# Straingauge.net
KiCad netlist of a schematic drawn in Altium Designer
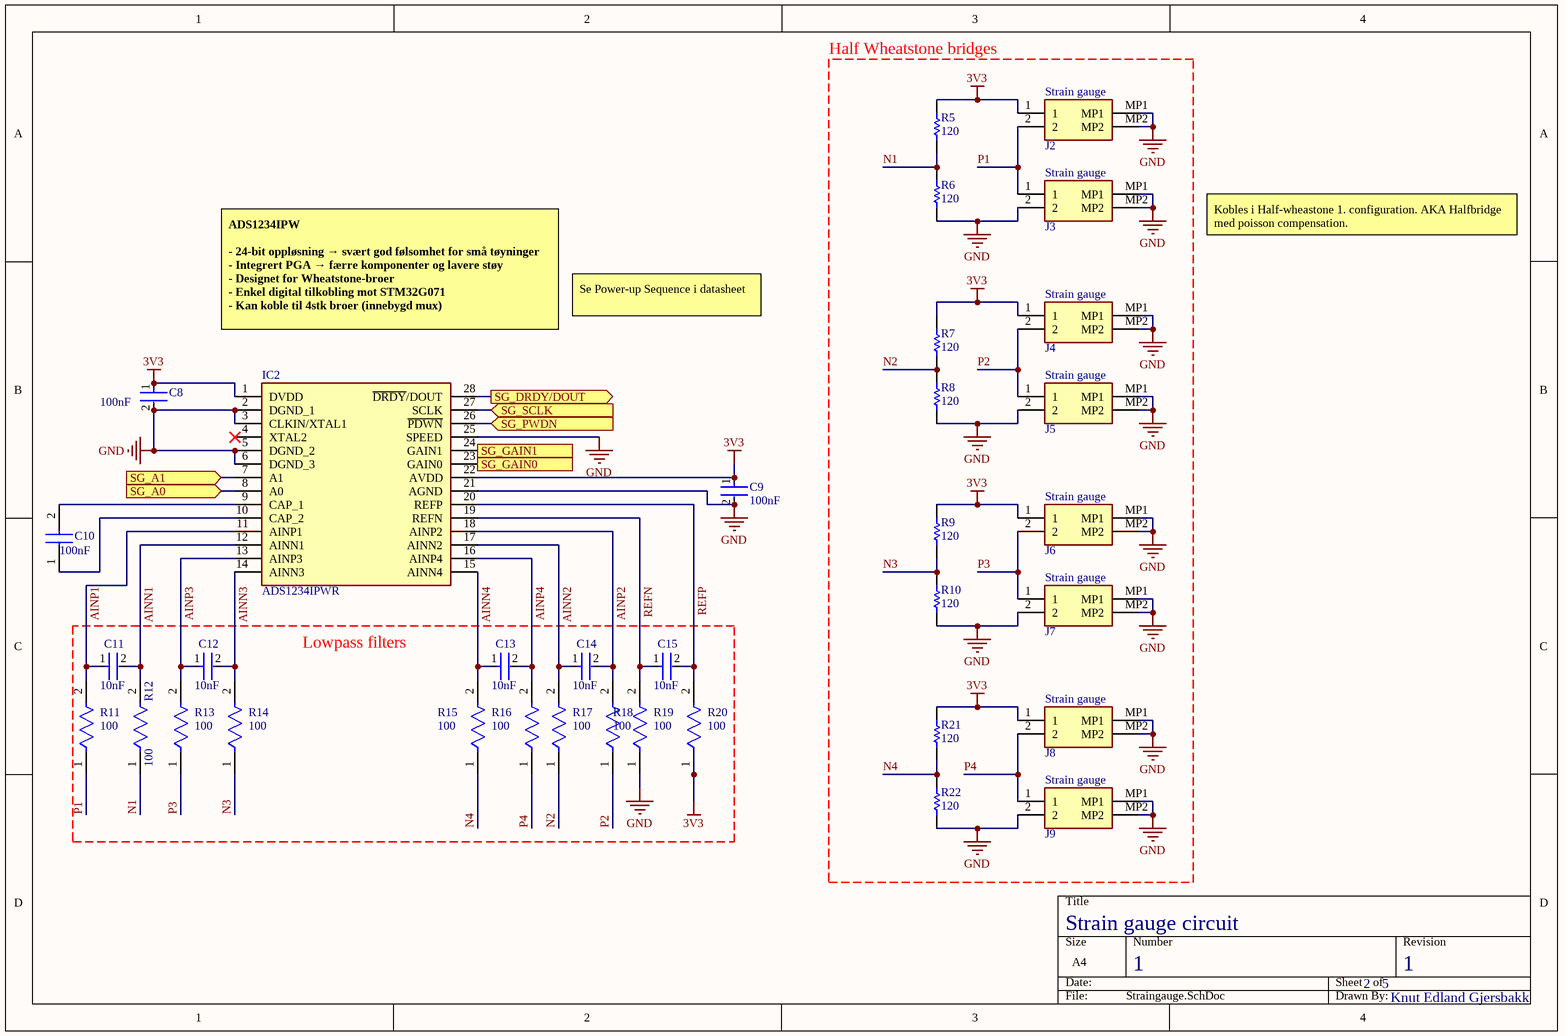
[diagram p0: Straingauge.SchDoc]

(export (version "E")
  (design (tool "Eeschema 10.0.6"))
  (components
    (comp (ref "C8")
      (value "100nF")
      (footprint "FP-CL10-IPC_C")
      (description "Cap Ceramic 100nF 16V X7R ±10% Pad SMD 0603 +125°C T/R\r\nCL10B104KO8WPNC")
      (fields (field (name "TOLERANCE") "10%"))
      (libsource (lib "Altium Content Vault") (part "b4654b650e69147ec39a6b967a45e02"))
    )
    (comp (ref "C9")
      (value "100nF")
      (footprint "FP-CL10-IPC_C")
      (description "Cap Ceramic 100nF 16V X7R ±10% Pad SMD 0603 +125°C T/R\r\nCL10B104KO8WPNC")
      (fields (field (name "TOLERANCE") "10%"))
      (libsource (lib "Altium Content Vault") (part "b4654b650e69147ec39a6b967a45e02"))
    )
    (comp (ref "C10")
      (value "100nF")
      (footprint "SamacSys:CAPC3216X180N")
      (description "Capacitor")
      (fields
        (field (name "MANUFACTURER_PART_NUMBER") "GRM31C5C1E104JA01L")
        (field (name "MOUSER PART NUMBER") "81-GRM31C5C1E104JA01")
      )
      (libsource (lib "*") (part "GRM31C5C1E104JA01L"))
    )
    (comp (ref "C11")
      (value "GRM2195C1H103JA01D")
      (footprint "FP-GRM219-0_1-IPC_B")
      (description "Chip Multilayer Ceramic Capacitors for General Purpose, 0805, 10000pF, C0G, 30ppm/°C, 5%, 50V")
      (fields
        (field (name "VOLTAGE") "50V")
        (field (name "TOLERANCE") "5%")
        (field (name "CAPACITANCE") "10nF")
      )
      (libsource (lib "Altium Content Vault") (part "02cd4be3c70576c341d710602a673aa"))
    )
    (comp (ref "C12")
      (value "GRM2195C1H103JA01D")
      (footprint "FP-GRM219-0_1-IPC_B")
      (description "Chip Multilayer Ceramic Capacitors for General Purpose, 0805, 10000pF, C0G, 30ppm/°C, 5%, 50V")
      (fields
        (field (name "VOLTAGE") "50V")
        (field (name "TOLERANCE") "5%")
        (field (name "CAPACITANCE") "10nF")
      )
      (libsource (lib "Altium Content Vault") (part "02cd4be3c70576c341d710602a673aa"))
    )
    (comp (ref "C13")
      (value "GRM2195C1H103JA01D")
      (footprint "FP-GRM219-0_1-IPC_B")
      (description "Chip Multilayer Ceramic Capacitors for General Purpose, 0805, 10000pF, C0G, 30ppm/°C, 5%, 50V")
      (fields
        (field (name "VOLTAGE") "50V")
        (field (name "TOLERANCE") "5%")
        (field (name "CAPACITANCE") "10nF")
      )
      (libsource (lib "Altium Content Vault") (part "02cd4be3c70576c341d710602a673aa"))
    )
    (comp (ref "C14")
      (value "GRM2195C1H103JA01D")
      (footprint "FP-GRM219-0_1-IPC_B")
      (description "Chip Multilayer Ceramic Capacitors for General Purpose, 0805, 10000pF, C0G, 30ppm/°C, 5%, 50V")
      (fields
        (field (name "VOLTAGE") "50V")
        (field (name "TOLERANCE") "5%")
        (field (name "CAPACITANCE") "10nF")
      )
      (libsource (lib "Altium Content Vault") (part "02cd4be3c70576c341d710602a673aa"))
    )
    (comp (ref "C15")
      (value "GRM2195C1H103JA01D")
      (footprint "FP-GRM219-0_1-IPC_B")
      (description "Chip Multilayer Ceramic Capacitors for General Purpose, 0805, 10000pF, C0G, 30ppm/°C, 5%, 50V")
      (fields
        (field (name "VOLTAGE") "50V")
        (field (name "TOLERANCE") "5%")
        (field (name "CAPACITANCE") "10nF")
      )
      (libsource (lib "Altium Content Vault") (part "02cd4be3c70576c341d710602a673aa"))
    )
    (comp (ref "IC2")
      (value "ADS1234IPWR")
      (footprint "SamacSys:SOP65P640X120-28N")
      (description "Integrated Circuit")
      (fields (field (name "MOUSER PART NUMBER") "595-ADS1234IPWR"))
      (libsource (lib "*") (part "ADS1234IPWR"))
    )
    (comp (ref "J2")
      (value "S2B-PH-SM4-TB_LF__SN_")
      (footprint "SamacSys:S2BPHSM4TBLFSN")
      (description "Connector")
      (fields (field (name "MANUFACTURER_PART_NUMBER") "S2B-PH-SM4-TB(LF)(SN)"))
      (libsource (lib "*") (part "S2B-PH-SM4-TB_LF__SN_"))
    )
    (comp (ref "J3")
      (value "S2B-PH-SM4-TB_LF__SN_")
      (footprint "SamacSys:S2BPHSM4TBLFSN")
      (description "Connector")
      (fields (field (name "MANUFACTURER_PART_NUMBER") "S2B-PH-SM4-TB(LF)(SN)"))
      (libsource (lib "*") (part "S2B-PH-SM4-TB_LF__SN_"))
    )
    (comp (ref "J4")
      (value "S2B-PH-SM4-TB_LF__SN_")
      (footprint "SamacSys:S2BPHSM4TBLFSN")
      (description "Connector")
      (fields (field (name "MANUFACTURER_PART_NUMBER") "S2B-PH-SM4-TB(LF)(SN)"))
      (libsource (lib "*") (part "S2B-PH-SM4-TB_LF__SN_"))
    )
    (comp (ref "J5")
      (value "S2B-PH-SM4-TB_LF__SN_")
      (footprint "SamacSys:S2BPHSM4TBLFSN")
      (description "Connector")
      (fields (field (name "MANUFACTURER_PART_NUMBER") "S2B-PH-SM4-TB(LF)(SN)"))
      (libsource (lib "*") (part "S2B-PH-SM4-TB_LF__SN_"))
    )
    (comp (ref "J6")
      (value "S2B-PH-SM4-TB_LF__SN_")
      (footprint "SamacSys:S2BPHSM4TBLFSN")
      (description "Connector")
      (fields (field (name "MANUFACTURER_PART_NUMBER") "S2B-PH-SM4-TB(LF)(SN)"))
      (libsource (lib "*") (part "S2B-PH-SM4-TB_LF__SN_"))
    )
    (comp (ref "J7")
      (value "S2B-PH-SM4-TB_LF__SN_")
      (footprint "SamacSys:S2BPHSM4TBLFSN")
      (description "Connector")
      (fields (field (name "MANUFACTURER_PART_NUMBER") "S2B-PH-SM4-TB(LF)(SN)"))
      (libsource (lib "*") (part "S2B-PH-SM4-TB_LF__SN_"))
    )
    (comp (ref "J8")
      (value "S2B-PH-SM4-TB_LF__SN_")
      (footprint "SamacSys:S2BPHSM4TBLFSN")
      (description "Connector")
      (fields (field (name "MANUFACTURER_PART_NUMBER") "S2B-PH-SM4-TB(LF)(SN)"))
      (libsource (lib "*") (part "S2B-PH-SM4-TB_LF__SN_"))
    )
    (comp (ref "J9")
      (value "S2B-PH-SM4-TB_LF__SN_")
      (footprint "SamacSys:S2BPHSM4TBLFSN")
      (description "Connector")
      (fields (field (name "MANUFACTURER_PART_NUMBER") "S2B-PH-SM4-TB(LF)(SN)"))
      (libsource (lib "*") (part "S2B-PH-SM4-TB_LF__SN_"))
    )
    (comp (ref "R5")
      (value "120")
      (footprint "RESC2013X60X40ML20T25")
      (fields (field (name "MANUFACTURER") "Panasonic") (field (name "PART NUMBER") "ERA6AEB121V"))
      (libsource (lib "Altium Content Vault") (part "RES"))
    )
    (comp (ref "R6")
      (value "120")
      (footprint "RESC2013X60X40ML20T25")
      (fields (field (name "MANUFACTURER") "Panasonic") (field (name "PART NUMBER") "ERA6AEB121V"))
      (libsource (lib "Altium Content Vault") (part "RES"))
    )
    (comp (ref "R7")
      (value "120")
      (footprint "RESC2013X60X40ML20T25")
      (fields (field (name "MANUFACTURER") "Panasonic") (field (name "PART NUMBER") "ERA6AEB121V"))
      (libsource (lib "Altium Content Vault") (part "RES"))
    )
    (comp (ref "R8")
      (value "120")
      (footprint "RESC2013X60X40ML20T25")
      (fields (field (name "MANUFACTURER") "Panasonic") (field (name "PART NUMBER") "ERA6AEB121V"))
      (libsource (lib "Altium Content Vault") (part "RES"))
    )
    (comp (ref "R9")
      (value "120")
      (footprint "RESC2013X60X40ML20T25")
      (fields (field (name "MANUFACTURER") "Panasonic") (field (name "PART NUMBER") "ERA6AEB121V"))
      (libsource (lib "Altium Content Vault") (part "RES"))
    )
    (comp (ref "R10")
      (value "120")
      (footprint "RESC2013X60X40ML20T25")
      (fields (field (name "MANUFACTURER") "Panasonic") (field (name "PART NUMBER") "ERA6AEB121V"))
      (libsource (lib "Altium Content Vault") (part "RES"))
    )
    (comp (ref "R11")
      (value "100")
      (footprint "FP-ERA3A-IPC_B")
      (description "RES SMD 100 OHM 0.1% 1/10W 0603")
      (fields (field (name "TOLERANCE") "0.1%"))
      (libsource (lib "Altium Content Vault") (part "1029c3af85768c4190bb7ad29bc67b5"))
    )
    (comp (ref "R12")
      (value "100")
      (footprint "FP-ERA3A-IPC_B")
      (description "RES SMD 100 OHM 0.1% 1/10W 0603")
      (fields (field (name "TOLERANCE") "0.1%"))
      (libsource (lib "Altium Content Vault") (part "1029c3af85768c4190bb7ad29bc67b5"))
    )
    (comp (ref "R13")
      (value "100")
      (footprint "FP-ERA3A-IPC_B")
      (description "RES SMD 100 OHM 0.1% 1/10W 0603")
      (fields (field (name "TOLERANCE") "0.1%"))
      (libsource (lib "Altium Content Vault") (part "1029c3af85768c4190bb7ad29bc67b5"))
    )
    (comp (ref "R14")
      (value "100")
      (footprint "FP-ERA3A-IPC_B")
      (description "RES SMD 100 OHM 0.1% 1/10W 0603")
      (fields (field (name "TOLERANCE") "0.1%"))
      (libsource (lib "Altium Content Vault") (part "1029c3af85768c4190bb7ad29bc67b5"))
    )
    (comp (ref "R15")
      (value "100")
      (footprint "FP-ERA3A-IPC_B")
      (description "RES SMD 100 OHM 0.1% 1/10W 0603")
      (fields (field (name "TOLERANCE") "0.1%"))
      (libsource (lib "Altium Content Vault") (part "1029c3af85768c4190bb7ad29bc67b5"))
    )
    (comp (ref "R16")
      (value "100")
      (footprint "FP-ERA3A-IPC_B")
      (description "RES SMD 100 OHM 0.1% 1/10W 0603")
      (fields (field (name "TOLERANCE") "0.1%"))
      (libsource (lib "Altium Content Vault") (part "1029c3af85768c4190bb7ad29bc67b5"))
    )
    (comp (ref "R17")
      (value "100")
      (footprint "FP-ERA3A-IPC_B")
      (description "RES SMD 100 OHM 0.1% 1/10W 0603")
      (fields (field (name "TOLERANCE") "0.1%"))
      (libsource (lib "Altium Content Vault") (part "1029c3af85768c4190bb7ad29bc67b5"))
    )
    (comp (ref "R18")
      (value "100")
      (footprint "FP-ERA3A-IPC_B")
      (description "RES SMD 100 OHM 0.1% 1/10W 0603")
      (fields (field (name "TOLERANCE") "0.1%"))
      (libsource (lib "Altium Content Vault") (part "1029c3af85768c4190bb7ad29bc67b5"))
    )
    (comp (ref "R19")
      (value "100")
      (footprint "FP-ERA3A-IPC_B")
      (description "RES SMD 100 OHM 0.1% 1/10W 0603")
      (fields (field (name "TOLERANCE") "0.1%"))
      (libsource (lib "Altium Content Vault") (part "1029c3af85768c4190bb7ad29bc67b5"))
    )
    (comp (ref "R20")
      (value "100")
      (footprint "FP-ERA3A-IPC_B")
      (description "RES SMD 100 OHM 0.1% 1/10W 0603")
      (fields (field (name "TOLERANCE") "0.1%"))
      (libsource (lib "Altium Content Vault") (part "1029c3af85768c4190bb7ad29bc67b5"))
    )
    (comp (ref "R21")
      (value "120")
      (footprint "RESC2013X60X40ML20T25")
      (fields (field (name "MANUFACTURER") "Panasonic") (field (name "PART NUMBER") "ERA6AEB121V"))
      (libsource (lib "Altium Content Vault") (part "RES"))
    )
    (comp (ref "R22")
      (value "120")
      (footprint "RESC2013X60X40ML20T25")
      (fields (field (name "MANUFACTURER") "Panasonic") (field (name "PART NUMBER") "ERA6AEB121V"))
      (libsource (lib "Altium Content Vault") (part "RES"))
    )
  )
  (nets
    (net (code "1") (name "/AINN1") (class "Default")
      (node (ref "C11") (pin "2") (pinfunction "2_2") (pintype "passive"))
      (node (ref "IC2") (pin "12") (pinfunction "AINN1_12") (pintype "passive"))
      (node (ref "R12") (pin "2") (pinfunction "2_2") (pintype "passive"))
    )
    (net (code "2") (name "/AINN2") (class "Default")
      (node (ref "C14") (pin "1") (pinfunction "1_1") (pintype "passive"))
      (node (ref "IC2") (pin "17") (pinfunction "AINN2_17") (pintype "passive"))
      (node (ref "R17") (pin "2") (pinfunction "2_2") (pintype "passive"))
    )
    (net (code "3") (name "/AINN3") (class "Default")
      (node (ref "C12") (pin "2") (pinfunction "2_2") (pintype "passive"))
      (node (ref "IC2") (pin "14") (pinfunction "AINN3_14") (pintype "passive"))
      (node (ref "R14") (pin "2") (pinfunction "2_2") (pintype "passive"))
    )
    (net (code "4") (name "/AINN4") (class "Default")
      (node (ref "C13") (pin "1") (pinfunction "1_1") (pintype "passive"))
      (node (ref "IC2") (pin "15") (pinfunction "AINN4_15") (pintype "passive"))
      (node (ref "R15") (pin "2") (pinfunction "2_2") (pintype "passive"))
    )
    (net (code "5") (name "/AINP1") (class "Default")
      (node (ref "C11") (pin "1") (pinfunction "1_1") (pintype "passive"))
      (node (ref "IC2") (pin "11") (pinfunction "AINP1_11") (pintype "passive"))
      (node (ref "R11") (pin "2") (pinfunction "2_2") (pintype "passive"))
    )
    (net (code "6") (name "/AINP2") (class "Default")
      (node (ref "C14") (pin "2") (pinfunction "2_2") (pintype "passive"))
      (node (ref "IC2") (pin "18") (pinfunction "AINP2_18") (pintype "passive"))
      (node (ref "R18") (pin "2") (pinfunction "2_2") (pintype "passive"))
    )
    (net (code "7") (name "/AINP3") (class "Default")
      (node (ref "C12") (pin "1") (pinfunction "1_1") (pintype "passive"))
      (node (ref "IC2") (pin "13") (pinfunction "AINP3_13") (pintype "passive"))
      (node (ref "R13") (pin "2") (pinfunction "2_2") (pintype "passive"))
    )
    (net (code "8") (name "/AINP4") (class "Default")
      (node (ref "C13") (pin "2") (pinfunction "2_2") (pintype "passive"))
      (node (ref "IC2") (pin "16") (pinfunction "AINP4_16") (pintype "passive"))
      (node (ref "R16") (pin "2") (pinfunction "2_2") (pintype "passive"))
    )
    (net (code "9") (name "/N1") (class "Default")
      (node (ref "R12") (pin "1") (pinfunction "1_1") (pintype "passive"))
      (node (ref "R5") (pin "1") (pinfunction "1_1") (pintype "passive"))
      (node (ref "R6") (pin "2") (pinfunction "2_2") (pintype "passive"))
    )
    (net (code "10") (name "/N2") (class "Default")
      (node (ref "R17") (pin "1") (pinfunction "1_1") (pintype "passive"))
      (node (ref "R7") (pin "1") (pinfunction "1_1") (pintype "passive"))
      (node (ref "R8") (pin "2") (pinfunction "2_2") (pintype "passive"))
    )
    (net (code "11") (name "/N3") (class "Default")
      (node (ref "R10") (pin "2") (pinfunction "2_2") (pintype "passive"))
      (node (ref "R14") (pin "1") (pinfunction "1_1") (pintype "passive"))
      (node (ref "R9") (pin "1") (pinfunction "1_1") (pintype "passive"))
    )
    (net (code "12") (name "/N4") (class "Default")
      (node (ref "R15") (pin "1") (pinfunction "1_1") (pintype "passive"))
      (node (ref "R21") (pin "1") (pinfunction "1_1") (pintype "passive"))
      (node (ref "R22") (pin "2") (pinfunction "2_2") (pintype "passive"))
    )
    (net (code "13") (name "/P1") (class "Default")
      (node (ref "J2") (pin "2") (pinfunction "2_2") (pintype "passive"))
      (node (ref "J3") (pin "1") (pinfunction "1_1") (pintype "passive"))
      (node (ref "R11") (pin "1") (pinfunction "1_1") (pintype "passive"))
    )
    (net (code "14") (name "/P2") (class "Default")
      (node (ref "J4") (pin "2") (pinfunction "2_2") (pintype "passive"))
      (node (ref "J5") (pin "1") (pinfunction "1_1") (pintype "passive"))
      (node (ref "R18") (pin "1") (pinfunction "1_1") (pintype "passive"))
    )
    (net (code "15") (name "/P3") (class "Default")
      (node (ref "J6") (pin "2") (pinfunction "2_2") (pintype "passive"))
      (node (ref "J7") (pin "1") (pinfunction "1_1") (pintype "passive"))
      (node (ref "R13") (pin "1") (pinfunction "1_1") (pintype "passive"))
    )
    (net (code "16") (name "/P4") (class "Default")
      (node (ref "J8") (pin "2") (pinfunction "2_2") (pintype "passive"))
      (node (ref "J9") (pin "1") (pinfunction "1_1") (pintype "passive"))
      (node (ref "R16") (pin "1") (pinfunction "1_1") (pintype "passive"))
    )
    (net (code "17") (name "/REFN") (class "Default")
      (node (ref "C15") (pin "1") (pinfunction "1_1") (pintype "passive"))
      (node (ref "IC2") (pin "19") (pinfunction "REFN_19") (pintype "passive"))
      (node (ref "R19") (pin "2") (pinfunction "2_2") (pintype "passive"))
    )
    (net (code "18") (name "/REFP") (class "Default")
      (node (ref "C15") (pin "2") (pinfunction "2_2") (pintype "passive"))
      (node (ref "IC2") (pin "20") (pinfunction "REFP_20") (pintype "passive"))
      (node (ref "R20") (pin "2") (pinfunction "2_2") (pintype "passive"))
    )
    (net (code "19") (name "/SG_A0") (class "Default")
      (node (ref "IC2") (pin "8") (pinfunction "A0_8") (pintype "passive"))
    )
    (net (code "20") (name "/SG_A1") (class "Default")
      (node (ref "IC2") (pin "7") (pinfunction "A1_7") (pintype "passive"))
    )
    (net (code "21") (name "/SG_DRDY{slash}DOUT") (class "Default")
      (node (ref "IC2") (pin "28") (pinfunction "~{DRDY}/DOUT_28") (pintype "passive"))
    )
    (net (code "22") (name "/SG_GAIN0") (class "Default")
      (node (ref "IC2") (pin "23") (pinfunction "GAIN0_23") (pintype "passive"))
    )
    (net (code "23") (name "/SG_GAIN1") (class "Default")
      (node (ref "IC2") (pin "24") (pinfunction "GAIN1_24") (pintype "passive"))
    )
    (net (code "24") (name "/SG_PWDN") (class "Default")
      (node (ref "IC2") (pin "26") (pinfunction "~{PDWN}_26") (pintype "passive"))
    )
    (net (code "25") (name "/SG_SCLK") (class "Default")
      (node (ref "IC2") (pin "27") (pinfunction "SCLK_27") (pintype "passive"))
    )
    (net (code "26") (name "3V3") (class "Default")
      (node (ref "C8") (pin "1") (pinfunction "1_1") (pintype "passive"))
      (node (ref "C9") (pin "1") (pinfunction "1_1") (pintype "passive"))
      (node (ref "IC2") (pin "1") (pinfunction "DVDD_1") (pintype "passive"))
      (node (ref "IC2") (pin "22") (pinfunction "AVDD_22") (pintype "passive"))
      (node (ref "J2") (pin "1") (pinfunction "1_1") (pintype "passive"))
      (node (ref "J4") (pin "1") (pinfunction "1_1") (pintype "passive"))
      (node (ref "J6") (pin "1") (pinfunction "1_1") (pintype "passive"))
      (node (ref "J8") (pin "1") (pinfunction "1_1") (pintype "passive"))
      (node (ref "R20") (pin "1") (pinfunction "1_1") (pintype "passive"))
      (node (ref "R21") (pin "2") (pinfunction "2_2") (pintype "passive"))
      (node (ref "R5") (pin "2") (pinfunction "2_2") (pintype "passive"))
      (node (ref "R7") (pin "2") (pinfunction "2_2") (pintype "passive"))
      (node (ref "R9") (pin "2") (pinfunction "2_2") (pintype "passive"))
    )
    (net (code "27") (name "GND") (class "Default")
      (node (ref "C8") (pin "2") (pinfunction "2_2") (pintype "passive"))
      (node (ref "C9") (pin "2") (pinfunction "2_2") (pintype "passive"))
      (node (ref "IC2") (pin "2") (pinfunction "DGND_1_2") (pintype "passive"))
      (node (ref "IC2") (pin "21") (pinfunction "AGND_21") (pintype "passive"))
      (node (ref "IC2") (pin "25") (pinfunction "SPEED_25") (pintype "passive"))
      (node (ref "IC2") (pin "3") (pinfunction "CLKIN/XTAL1_3") (pintype "passive"))
      (node (ref "IC2") (pin "5") (pinfunction "DGND_2_5") (pintype "passive"))
      (node (ref "IC2") (pin "6") (pinfunction "DGND_3_6") (pintype "passive"))
      (node (ref "J2") (pin "MP1") (pinfunction "MP1_MP1") (pintype "passive"))
      (node (ref "J2") (pin "MP2") (pinfunction "MP2_MP2") (pintype "passive"))
      (node (ref "J3") (pin "2") (pinfunction "2_2") (pintype "passive"))
      (node (ref "J3") (pin "MP1") (pinfunction "MP1_MP1") (pintype "passive"))
      (node (ref "J3") (pin "MP2") (pinfunction "MP2_MP2") (pintype "passive"))
      (node (ref "J4") (pin "MP1") (pinfunction "MP1_MP1") (pintype "passive"))
      (node (ref "J4") (pin "MP2") (pinfunction "MP2_MP2") (pintype "passive"))
      (node (ref "J5") (pin "2") (pinfunction "2_2") (pintype "passive"))
      (node (ref "J5") (pin "MP1") (pinfunction "MP1_MP1") (pintype "passive"))
      (node (ref "J5") (pin "MP2") (pinfunction "MP2_MP2") (pintype "passive"))
      (node (ref "J6") (pin "MP1") (pinfunction "MP1_MP1") (pintype "passive"))
      (node (ref "J6") (pin "MP2") (pinfunction "MP2_MP2") (pintype "passive"))
      (node (ref "J7") (pin "2") (pinfunction "2_2") (pintype "passive"))
      (node (ref "J7") (pin "MP1") (pinfunction "MP1_MP1") (pintype "passive"))
      (node (ref "J7") (pin "MP2") (pinfunction "MP2_MP2") (pintype "passive"))
      (node (ref "J8") (pin "MP1") (pinfunction "MP1_MP1") (pintype "passive"))
      (node (ref "J8") (pin "MP2") (pinfunction "MP2_MP2") (pintype "passive"))
      (node (ref "J9") (pin "2") (pinfunction "2_2") (pintype "passive"))
      (node (ref "J9") (pin "MP1") (pinfunction "MP1_MP1") (pintype "passive"))
      (node (ref "J9") (pin "MP2") (pinfunction "MP2_MP2") (pintype "passive"))
      (node (ref "R10") (pin "1") (pinfunction "1_1") (pintype "passive"))
      (node (ref "R19") (pin "1") (pinfunction "1_1") (pintype "passive"))
      (node (ref "R22") (pin "1") (pinfunction "1_1") (pintype "passive"))
      (node (ref "R6") (pin "1") (pinfunction "1_1") (pintype "passive"))
      (node (ref "R8") (pin "1") (pinfunction "1_1") (pintype "passive"))
    )
    (net (code "28") (name "Net-(IC2-CAP_1)") (class "Default")
      (node (ref "C10") (pin "2") (pinfunction "2_2") (pintype "passive"))
      (node (ref "IC2") (pin "9") (pinfunction "CAP_1_9") (pintype "passive"))
    )
    (net (code "29") (name "Net-(IC2-CAP_2)") (class "Default")
      (node (ref "C10") (pin "1") (pinfunction "1_1") (pintype "passive"))
      (node (ref "IC2") (pin "10") (pinfunction "CAP_2_10") (pintype "passive"))
    )
    (net (code "30") (name "unconnected-(IC2-XTAL2-Pad4)") (class "Default")
      (node (ref "IC2") (pin "4") (pinfunction "XTAL2_4") (pintype "passive+no_connect"))
    )
  )
)
